# Clk.net
KiCad netlist of a schematic drawn in Altium Designer
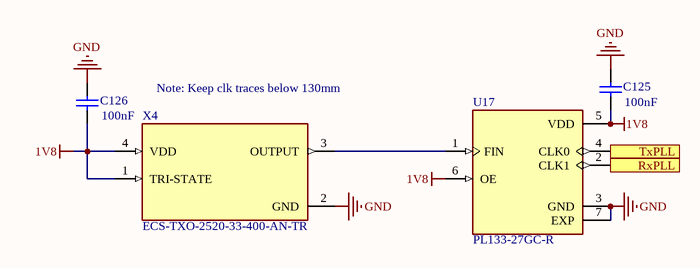
[diagram p0: Clk.SchDoc]

(export (version "E")
  (design (tool "Eeschema 10.0.6"))
  (components
    (comp (ref "C125")
      (value "100nF")
      (footprint "0402-A")
      (description "Capacitor")
      (fields (field (name "Comment") "Cap") (field (name "PUBLISHER") "Altium Limited"))
      (libsource (lib "Miscellaneous Devices") (part "Cap"))
    )
    (comp (ref "C126")
      (value "100nF")
      (footprint "0402-A")
      (description "Capacitor")
      (fields (field (name "Comment") "Cap") (field (name "PUBLISHER") "Altium Limited"))
      (libsource (lib "Miscellaneous Devices") (part "Cap"))
    )
    (comp (ref "U17")
      (value "PL133-27GC-R")
      (footprint "SON40P130X200X60-7N")
      (description "Clock Fanout Buffer _Distribution_ IC 1:2 150MHz 6-UFDFN Exposed Pad")
      (fields (field (name "MF") "Microchip"))
      (libsource (lib "PL133-27GC-R") (part "PL133-27GC-R"))
    )
    (comp (ref "X4")
      (value "ECS-TXO-2520-33-400-AN-TR")
      (footprint "OSC_ECS-TXO-2520-33-400-AN-TR")
      (description "40MHz TCXO HCMOS Oscillator 3.3V Enable/Disable 4-SMD, No Lead")
      (fields (field (name "MF") "ECS Inc."))
      (libsource (lib "ECS-TXO-2520-33-400-AN-TR") (part "ECS-TXO-2520-33-400-AN-TR"))
    )
  )
  (nets
    (net (code "1") (name "/RxPLL") (class "Default")
      (node (ref "U17") (pin "2") (pinfunction "CLK1_2") (pintype "output"))
    )
    (net (code "2") (name "/TxPLL") (class "Default")
      (node (ref "U17") (pin "4") (pinfunction "CLK0_4") (pintype "output"))
    )
    (net (code "3") (name "1V8") (class "Default")
      (node (ref "C125") (pin "2") (pinfunction "2_2") (pintype "passive"))
      (node (ref "C126") (pin "2") (pinfunction "2_2") (pintype "passive"))
      (node (ref "U17") (pin "5") (pinfunction "VDD_5") (pintype "power_in"))
      (node (ref "U17") (pin "6") (pinfunction "OE_6") (pintype "input"))
      (node (ref "X4") (pin "1") (pinfunction "TRI-STATE_1") (pintype "input"))
      (node (ref "X4") (pin "4") (pinfunction "VDD_4") (pintype "input"))
    )
    (net (code "4") (name "GND") (class "Default")
      (node (ref "C125") (pin "1") (pinfunction "1_1") (pintype "passive"))
      (node (ref "C126") (pin "1") (pinfunction "1_1") (pintype "passive"))
      (node (ref "U17") (pin "3") (pinfunction "GND_3") (pintype "power_in"))
      (node (ref "U17") (pin "7") (pinfunction "EXP_7") (pintype "power_in"))
      (node (ref "X4") (pin "2") (pinfunction "GND_2") (pintype "power_in"))
    )
    (net (code "5") (name "Net-(U17-FIN)") (class "Default")
      (node (ref "U17") (pin "1") (pinfunction "FIN_1") (pintype "input"))
      (node (ref "X4") (pin "3") (pinfunction "OUTPUT_3") (pintype "output"))
    )
  )
)
